# Stacja_lutownicza_v2.net
KiCad netlist of a schematic drawn in EasyEDA
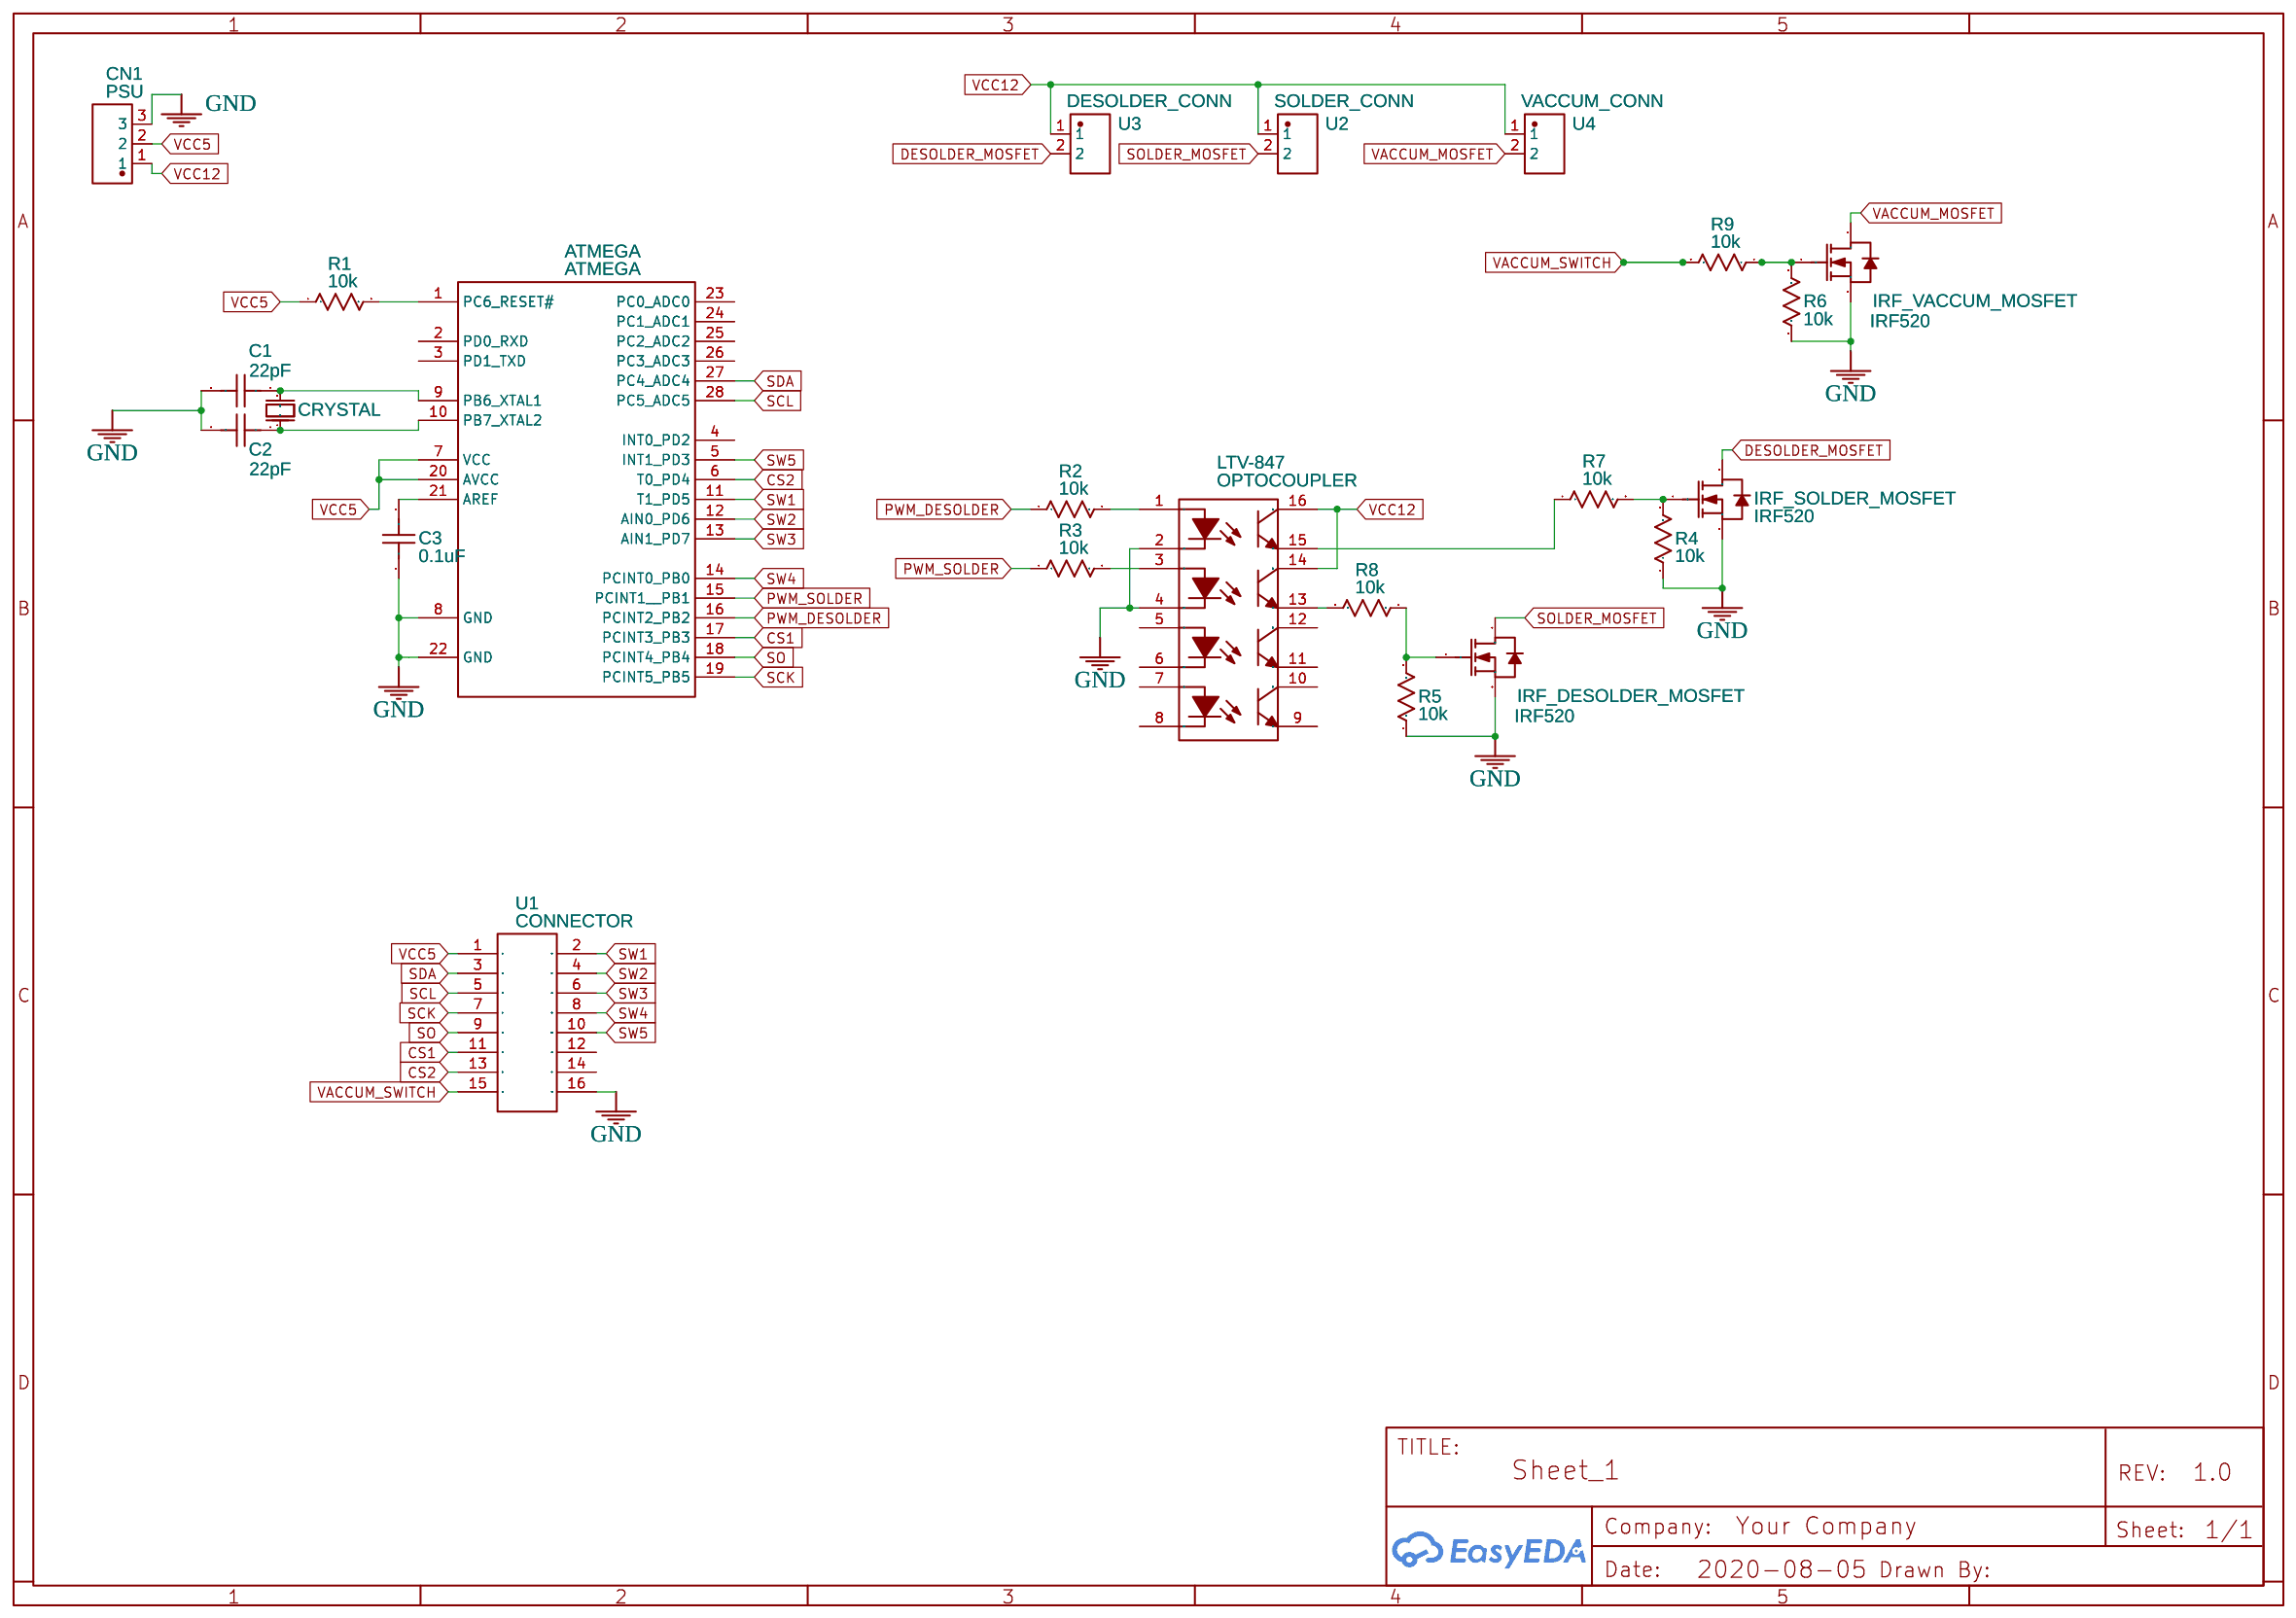
[diagram p0: schematic sheet]

(export (version "E")
  (design (tool "Eeschema 10.0.6"))
  (components
    (comp (ref "ATMEGA")
      (value "ATMEGA")
      (fields
        (field (name "BOM_Manufacturer Part") "ATMEGA328P-PU")
        (field (name "BOM_Supplier Part") "C33901")
      )
      (libsource (lib "") (part "ATMEGA328P-PU"))
    )
    (comp (ref "C1")
      (value "22pF")
      (fields
        (field (name "BOM_Manufacturer Part") "SMEC224J100M2")
        (field (name "BOM_Supplier Part") "C401099")
      )
      (libsource (lib "") (part "SMEC224J100M2"))
    )
    (comp (ref "C2")
      (value "22pF")
      (fields
        (field (name "BOM_Manufacturer Part") "SMEC224J100M2")
        (field (name "BOM_Supplier Part") "C401099")
      )
      (libsource (lib "") (part "SMEC224J100M2"))
    )
    (comp (ref "C3")
      (value "0.1uF")
      (fields
        (field (name "BOM_Manufacturer Part") "SMEC224J100M2")
        (field (name "BOM_Supplier Part") "C401099")
      )
      (libsource (lib "") (part "SMEC224J100M2_1"))
    )
    (comp (ref "CN1")
      (value "PSU")
      (fields
        (field (name "BOM_Manufacturer Part") "WJ103-5.00-3P")
        (field (name "BOM_Supplier Part") "C8427")
      )
      (libsource (lib "") (part "WJ103-5.00-3P"))
    )
    (comp (ref "IRF_DESOLDER_MOSFET")
      (value "IRF520")
      (fields (field (name "BOM_Manufacturer Part") "IRF520NPBF") (field (name "BOM_Supplier Part") "C2598"))
      (libsource (lib "") (part "IRF520NPBF"))
    )
    (comp (ref "IRF_SOLDER_MOSFET")
      (value "IRF520")
      (fields (field (name "BOM_Manufacturer Part") "IRF520NPBF") (field (name "BOM_Supplier Part") "C2598"))
      (libsource (lib "") (part "IRF520NPBF_2"))
    )
    (comp (ref "IRF_VACCUM_MOSFET")
      (value "IRF520")
      (fields (field (name "BOM_Manufacturer Part") "IRF520NPBF") (field (name "BOM_Supplier Part") "C2598"))
      (libsource (lib "") (part "IRF520NPBF_1"))
    )
    (comp (ref "LTV-847")
      (value "OPTOCOUPLER")
      (fields (field (name "BOM_Manufacturer Part") "LTV-847") (field (name "BOM_Supplier Part") "C10794"))
      (libsource (lib "") (part "LTV-847"))
    )
    (comp (ref "R1")
      (value "10k")
      (fields
        (field (name "BOM_Manufacturer Part") "MCF 0.25W 10K")
        (field (name "BOM_Supplier Part") "9339116")
      )
      (libsource (lib "") (part "10k_2"))
    )
    (comp (ref "R2")
      (value "10k")
      (fields
        (field (name "BOM_Manufacturer Part") "MCF 0.25W 10K")
        (field (name "BOM_Supplier Part") "9339116")
      )
      (libsource (lib "") (part "10k_2"))
    )
    (comp (ref "R3")
      (value "10k")
      (fields
        (field (name "BOM_Manufacturer Part") "MCF 0.25W 10K")
        (field (name "BOM_Supplier Part") "9339116")
      )
      (libsource (lib "") (part "10k_2"))
    )
    (comp (ref "R4")
      (value "10k")
      (fields
        (field (name "BOM_Manufacturer Part") "MCF 0.25W 10K")
        (field (name "BOM_Supplier Part") "9339116")
      )
      (libsource (lib "") (part "10k_1"))
    )
    (comp (ref "R5")
      (value "10k")
      (fields
        (field (name "BOM_Manufacturer Part") "MCF 0.25W 10K")
        (field (name "BOM_Supplier Part") "9339116")
      )
      (libsource (lib "") (part "10k_1"))
    )
    (comp (ref "R6")
      (value "10k")
      (fields
        (field (name "BOM_Manufacturer Part") "MCF 0.25W 10K")
        (field (name "BOM_Supplier Part") "9339116")
      )
      (libsource (lib "") (part "10k_1"))
    )
    (comp (ref "R7")
      (value "10k")
      (fields
        (field (name "BOM_Manufacturer Part") "MCF 0.25W 10K")
        (field (name "BOM_Supplier Part") "9339116")
      )
      (libsource (lib "") (part "10k_2"))
    )
    (comp (ref "R8")
      (value "10k")
      (fields
        (field (name "BOM_Manufacturer Part") "MCF 0.25W 10K")
        (field (name "BOM_Supplier Part") "9339116")
      )
      (libsource (lib "") (part "10k"))
    )
    (comp (ref "R9")
      (value "10k")
      (fields
        (field (name "BOM_Manufacturer Part") "MCF 0.25W 10K")
        (field (name "BOM_Supplier Part") "9339116")
      )
      (libsource (lib "") (part "10k"))
    )
    (comp (ref "U1") (value "CONNECTOR") (libsource (lib "") (part "IDC16 2.54 28x8.7 mm")))
    (comp (ref "U2")
      (value "SOLDER_CONN")
      (fields
        (field (name "BOM_Manufacturer Part") "JL301-50002U02")
        (field (name "BOM_Supplier Part") "C395214")
      )
      (libsource (lib "") (part "JL301-50002U02"))
    )
    (comp (ref "U3")
      (value "DESOLDER_CONN")
      (fields
        (field (name "BOM_Manufacturer Part") "JL301-50002U02")
        (field (name "BOM_Supplier Part") "C395214")
      )
      (libsource (lib "") (part "JL301-50002U02"))
    )
    (comp (ref "U4")
      (value "VACCUM_CONN")
      (fields
        (field (name "BOM_Manufacturer Part") "JL301-50002U02")
        (field (name "BOM_Supplier Part") "C395214")
      )
      (libsource (lib "") (part "JL301-50002U02"))
    )
    (comp (ref "X1")
      (value "CRYSTAL")
      (fields
        (field (name "BOM_Manufacturer Part") "49S9M20PF20PPMROHS")
        (field (name "BOM_Supplier Part") "C52064")
      )
      (libsource (lib "") (part "49S9M20PF20PPMROHS"))
    )
  )
  (nets
    (net (code "1") (name "CS1") (class "Default")
      (node (ref "ATMEGA") (pin "17") (pinfunction "PCINT3_PB3_17") (pintype "bidirectional"))
      (node (ref "U1") (pin "11") (pinfunction "11_11") (pintype "unspecified"))
    )
    (net (code "2") (name "CS2") (class "Default")
      (node (ref "ATMEGA") (pin "6") (pinfunction "T0_PD4_6") (pintype "bidirectional"))
      (node (ref "U1") (pin "13") (pinfunction "13_13") (pintype "unspecified"))
    )
    (net (code "3") (name "DESOLDER_MOSFET") (class "Default")
      (node (ref "IRF_SOLDER_MOSFET") (pin "2") (pinfunction "D_2") (pintype "unspecified"))
      (node (ref "U3") (pin "2") (pinfunction "2_2") (pintype "unspecified"))
    )
    (net (code "4") (name "GND") (class "Default")
      (node (ref "ATMEGA") (pin "22") (pinfunction "GND_22") (pintype "passive"))
      (node (ref "ATMEGA") (pin "8") (pinfunction "GND_8") (pintype "passive"))
      (node (ref "C1") (pin "2") (pinfunction "2_2") (pintype "unspecified"))
      (node (ref "C2") (pin "2") (pinfunction "2_2") (pintype "unspecified"))
      (node (ref "C3") (pin "2") (pinfunction "2_2") (pintype "unspecified"))
      (node (ref "CN1") (pin "3") (pinfunction "3_3") (pintype "unspecified"))
      (node (ref "IRF_DESOLDER_MOSFET") (pin "3") (pinfunction "S_3") (pintype "unspecified"))
      (node (ref "IRF_SOLDER_MOSFET") (pin "3") (pinfunction "S_3") (pintype "unspecified"))
      (node (ref "IRF_VACCUM_MOSFET") (pin "3") (pinfunction "S_3") (pintype "unspecified"))
      (node (ref "LTV-847") (pin "2") (pinfunction "CAT_2") (pintype "unspecified"))
      (node (ref "LTV-847") (pin "4") (pinfunction "CAT_4") (pintype "unspecified"))
      (node (ref "R4") (pin "1") (pinfunction "1_1") (pintype "unspecified"))
      (node (ref "R5") (pin "1") (pinfunction "1_1") (pintype "unspecified"))
      (node (ref "R6") (pin "1") (pinfunction "1_1") (pintype "unspecified"))
      (node (ref "U1") (pin "16") (pinfunction "16_16") (pintype "unspecified"))
    )
    (net (code "5") (name "Net-(ATMEGA-AREF)") (class "Default")
      (node (ref "ATMEGA") (pin "21") (pinfunction "AREF_21") (pintype "passive"))
      (node (ref "C3") (pin "1") (pinfunction "1_1") (pintype "unspecified"))
    )
    (net (code "6") (name "Net-(ATMEGA-PB6_XTAL1)") (class "Default")
      (node (ref "ATMEGA") (pin "9") (pinfunction "PB6_XTAL1_9") (pintype "bidirectional"))
      (node (ref "C1") (pin "1") (pinfunction "1_1") (pintype "unspecified"))
      (node (ref "X1") (pin "2") (pinfunction "OSC2_2") (pintype "input"))
    )
    (net (code "7") (name "Net-(ATMEGA-PB7_XTAL2)") (class "Default")
      (node (ref "ATMEGA") (pin "10") (pinfunction "PB7_XTAL2_10") (pintype "bidirectional"))
      (node (ref "C2") (pin "1") (pinfunction "1_1") (pintype "unspecified"))
      (node (ref "X1") (pin "1") (pinfunction "OSC1_1") (pintype "input"))
    )
    (net (code "8") (name "Net-(ATMEGA-PC6_RESET#)") (class "Default")
      (node (ref "ATMEGA") (pin "1") (pinfunction "PC6_RESET#_1") (pintype "bidirectional"))
      (node (ref "R1") (pin "2") (pinfunction "2_2") (pintype "unspecified"))
    )
    (net (code "9") (name "Net-(IRF_DESOLDER_MOSFET-G)") (class "Default")
      (node (ref "IRF_DESOLDER_MOSFET") (pin "1") (pinfunction "G_1") (pintype "unspecified"))
      (node (ref "R5") (pin "2") (pinfunction "2_2") (pintype "unspecified"))
      (node (ref "R8") (pin "1") (pinfunction "1_1") (pintype "unspecified"))
    )
    (net (code "10") (name "Net-(IRF_SOLDER_MOSFET-G)") (class "Default")
      (node (ref "IRF_SOLDER_MOSFET") (pin "1") (pinfunction "G_1") (pintype "unspecified"))
      (node (ref "R4") (pin "2") (pinfunction "2_2") (pintype "unspecified"))
      (node (ref "R7") (pin "2") (pinfunction "2_2") (pintype "unspecified"))
    )
    (net (code "11") (name "Net-(IRF_VACCUM_MOSFET-G)") (class "Default")
      (node (ref "IRF_VACCUM_MOSFET") (pin "1") (pinfunction "G_1") (pintype "unspecified"))
      (node (ref "R6") (pin "2") (pinfunction "2_2") (pintype "unspecified"))
      (node (ref "R9") (pin "1") (pinfunction "1_1") (pintype "unspecified"))
    )
    (net (code "12") (name "Net-(LTV-847-AN-Pad1)") (class "Default")
      (node (ref "LTV-847") (pin "1") (pinfunction "AN_1") (pintype "unspecified"))
      (node (ref "R2") (pin "2") (pinfunction "2_2") (pintype "unspecified"))
    )
    (net (code "13") (name "Net-(LTV-847-AN-Pad3)") (class "Default")
      (node (ref "LTV-847") (pin "3") (pinfunction "AN_3") (pintype "unspecified"))
      (node (ref "R3") (pin "2") (pinfunction "2_2") (pintype "unspecified"))
    )
    (net (code "14") (name "Net-(LTV-847-EM-Pad13)") (class "Default")
      (node (ref "LTV-847") (pin "13") (pinfunction "EM_13") (pintype "unspecified"))
      (node (ref "R8") (pin "2") (pinfunction "2_2") (pintype "unspecified"))
    )
    (net (code "15") (name "Net-(LTV-847-EM-Pad15)") (class "Default")
      (node (ref "LTV-847") (pin "15") (pinfunction "EM_15") (pintype "unspecified"))
      (node (ref "R7") (pin "1") (pinfunction "1_1") (pintype "unspecified"))
    )
    (net (code "16") (name "PWM_DESOLDER") (class "Default")
      (node (ref "ATMEGA") (pin "16") (pinfunction "PCINT2_PB2_16") (pintype "bidirectional"))
      (node (ref "R2") (pin "1") (pinfunction "1_1") (pintype "unspecified"))
    )
    (net (code "17") (name "PWM_SOLDER") (class "Default")
      (node (ref "ATMEGA") (pin "15") (pinfunction "PCINT1__PB1_15") (pintype "bidirectional"))
      (node (ref "R3") (pin "1") (pinfunction "1_1") (pintype "unspecified"))
    )
    (net (code "18") (name "SCK") (class "Default")
      (node (ref "ATMEGA") (pin "19") (pinfunction "PCINT5_PB5_19") (pintype "bidirectional"))
      (node (ref "U1") (pin "7") (pinfunction "P7_7") (pintype "unspecified"))
    )
    (net (code "19") (name "SCL") (class "Default")
      (node (ref "ATMEGA") (pin "28") (pinfunction "PC5_ADC5_28") (pintype "bidirectional"))
      (node (ref "U1") (pin "5") (pinfunction "P5_5") (pintype "unspecified"))
    )
    (net (code "20") (name "SDA") (class "Default")
      (node (ref "ATMEGA") (pin "27") (pinfunction "PC4_ADC4_27") (pintype "bidirectional"))
      (node (ref "U1") (pin "3") (pinfunction "P3_3") (pintype "unspecified"))
    )
    (net (code "21") (name "SO") (class "Default")
      (node (ref "ATMEGA") (pin "18") (pinfunction "PCINT4_PB4_18") (pintype "bidirectional"))
      (node (ref "U1") (pin "9") (pinfunction "P9_9") (pintype "unspecified"))
    )
    (net (code "22") (name "SOLDER_MOSFET") (class "Default")
      (node (ref "IRF_DESOLDER_MOSFET") (pin "2") (pinfunction "D_2") (pintype "unspecified"))
      (node (ref "U2") (pin "2") (pinfunction "2_2") (pintype "unspecified"))
    )
    (net (code "23") (name "SW1") (class "Default")
      (node (ref "ATMEGA") (pin "11") (pinfunction "T1_PD5_11") (pintype "bidirectional"))
      (node (ref "U1") (pin "2") (pinfunction "P2_2") (pintype "unspecified"))
    )
    (net (code "24") (name "SW2") (class "Default")
      (node (ref "ATMEGA") (pin "12") (pinfunction "AIN0_PD6_12") (pintype "bidirectional"))
      (node (ref "U1") (pin "4") (pinfunction "P4_4") (pintype "unspecified"))
    )
    (net (code "25") (name "SW3") (class "Default")
      (node (ref "ATMEGA") (pin "13") (pinfunction "AIN1_PD7_13") (pintype "bidirectional"))
      (node (ref "U1") (pin "6") (pinfunction "P6_6") (pintype "unspecified"))
    )
    (net (code "26") (name "SW4") (class "Default")
      (node (ref "ATMEGA") (pin "14") (pinfunction "PCINT0_PB0_14") (pintype "bidirectional"))
      (node (ref "U1") (pin "8") (pinfunction "P8_8") (pintype "unspecified"))
    )
    (net (code "27") (name "SW5") (class "Default")
      (node (ref "ATMEGA") (pin "5") (pinfunction "INT1_PD3_5") (pintype "bidirectional"))
      (node (ref "U1") (pin "10") (pinfunction "P10_10") (pintype "unspecified"))
    )
    (net (code "28") (name "VACCUM_MOSFET") (class "Default")
      (node (ref "IRF_VACCUM_MOSFET") (pin "2") (pinfunction "D_2") (pintype "unspecified"))
      (node (ref "U4") (pin "2") (pinfunction "2_2") (pintype "unspecified"))
    )
    (net (code "29") (name "VACCUM_SWITCH") (class "Default")
      (node (ref "R9") (pin "2") (pinfunction "2_2") (pintype "unspecified"))
      (node (ref "U1") (pin "15") (pinfunction "15_15") (pintype "unspecified"))
    )
    (net (code "30") (name "VCC5") (class "Default")
      (node (ref "ATMEGA") (pin "20") (pinfunction "AVCC_20") (pintype "passive"))
      (node (ref "ATMEGA") (pin "7") (pinfunction "VCC_7") (pintype "passive"))
      (node (ref "CN1") (pin "2") (pinfunction "2_2") (pintype "unspecified"))
      (node (ref "R1") (pin "1") (pinfunction "1_1") (pintype "unspecified"))
      (node (ref "U1") (pin "1") (pinfunction "P1_1") (pintype "unspecified"))
    )
    (net (code "31") (name "VCC12") (class "Default")
      (node (ref "CN1") (pin "1") (pinfunction "1_1") (pintype "unspecified"))
      (node (ref "LTV-847") (pin "14") (pinfunction "COL_14") (pintype "unspecified"))
      (node (ref "LTV-847") (pin "16") (pinfunction "COL_16") (pintype "unspecified"))
      (node (ref "U2") (pin "1") (pinfunction "1_1") (pintype "unspecified"))
      (node (ref "U3") (pin "1") (pinfunction "1_1") (pintype "unspecified"))
      (node (ref "U4") (pin "1") (pinfunction "1_1") (pintype "unspecified"))
    )
    (net (code "32") (name "unconnected-(ATMEGA-INT0_PD2-Pad4)") (class "Default")
      (node (ref "ATMEGA") (pin "4") (pinfunction "INT0_PD2_4") (pintype "bidirectional"))
    )
    (net (code "33") (name "unconnected-(ATMEGA-PC0_ADC0-Pad23)") (class "Default")
      (node (ref "ATMEGA") (pin "23") (pinfunction "PC0_ADC0_23") (pintype "bidirectional"))
    )
    (net (code "34") (name "unconnected-(ATMEGA-PC1_ADC1-Pad24)") (class "Default")
      (node (ref "ATMEGA") (pin "24") (pinfunction "PC1_ADC1_24") (pintype "bidirectional"))
    )
    (net (code "35") (name "unconnected-(ATMEGA-PC2_ADC2-Pad25)") (class "Default")
      (node (ref "ATMEGA") (pin "25") (pinfunction "PC2_ADC2_25") (pintype "bidirectional"))
    )
    (net (code "36") (name "unconnected-(ATMEGA-PC3_ADC3-Pad26)") (class "Default")
      (node (ref "ATMEGA") (pin "26") (pinfunction "PC3_ADC3_26") (pintype "bidirectional"))
    )
    (net (code "37") (name "unconnected-(ATMEGA-PD0_RXD-Pad2)") (class "Default")
      (node (ref "ATMEGA") (pin "2") (pinfunction "PD0_RXD_2") (pintype "bidirectional"))
    )
    (net (code "38") (name "unconnected-(ATMEGA-PD1_TXD-Pad3)") (class "Default")
      (node (ref "ATMEGA") (pin "3") (pinfunction "PD1_TXD_3") (pintype "bidirectional"))
    )
    (net (code "39") (name "unconnected-(LTV-847-AN-Pad5)") (class "Default")
      (node (ref "LTV-847") (pin "5") (pinfunction "AN_5") (pintype "unspecified"))
    )
    (net (code "40") (name "unconnected-(LTV-847-AN-Pad7)") (class "Default")
      (node (ref "LTV-847") (pin "7") (pinfunction "AN_7") (pintype "unspecified"))
    )
    (net (code "41") (name "unconnected-(LTV-847-CAT-Pad6)") (class "Default")
      (node (ref "LTV-847") (pin "6") (pinfunction "CAT_6") (pintype "unspecified"))
    )
    (net (code "42") (name "unconnected-(LTV-847-CAT-Pad8)") (class "Default")
      (node (ref "LTV-847") (pin "8") (pinfunction "CAT_8") (pintype "unspecified"))
    )
    (net (code "43") (name "unconnected-(LTV-847-COL-Pad10)") (class "Default")
      (node (ref "LTV-847") (pin "10") (pinfunction "COL_10") (pintype "unspecified"))
    )
    (net (code "44") (name "unconnected-(LTV-847-COL-Pad12)") (class "Default")
      (node (ref "LTV-847") (pin "12") (pinfunction "COL_12") (pintype "unspecified"))
    )
    (net (code "45") (name "unconnected-(LTV-847-EM-Pad9)") (class "Default")
      (node (ref "LTV-847") (pin "9") (pinfunction "EM_9") (pintype "unspecified"))
    )
    (net (code "46") (name "unconnected-(LTV-847-EM-Pad11)") (class "Default")
      (node (ref "LTV-847") (pin "11") (pinfunction "EM_11") (pintype "unspecified"))
    )
    (net (code "47") (name "unconnected-(U1-Pad12)") (class "Default")
      (node (ref "U1") (pin "12") (pinfunction "12_12") (pintype "unspecified"))
    )
    (net (code "48") (name "unconnected-(U1-Pad14)") (class "Default")
      (node (ref "U1") (pin "14") (pinfunction "14_14") (pintype "unspecified"))
    )
  )
)
